# SchematicDoc.net
KiCad netlist of a schematic drawn in Altium Designer
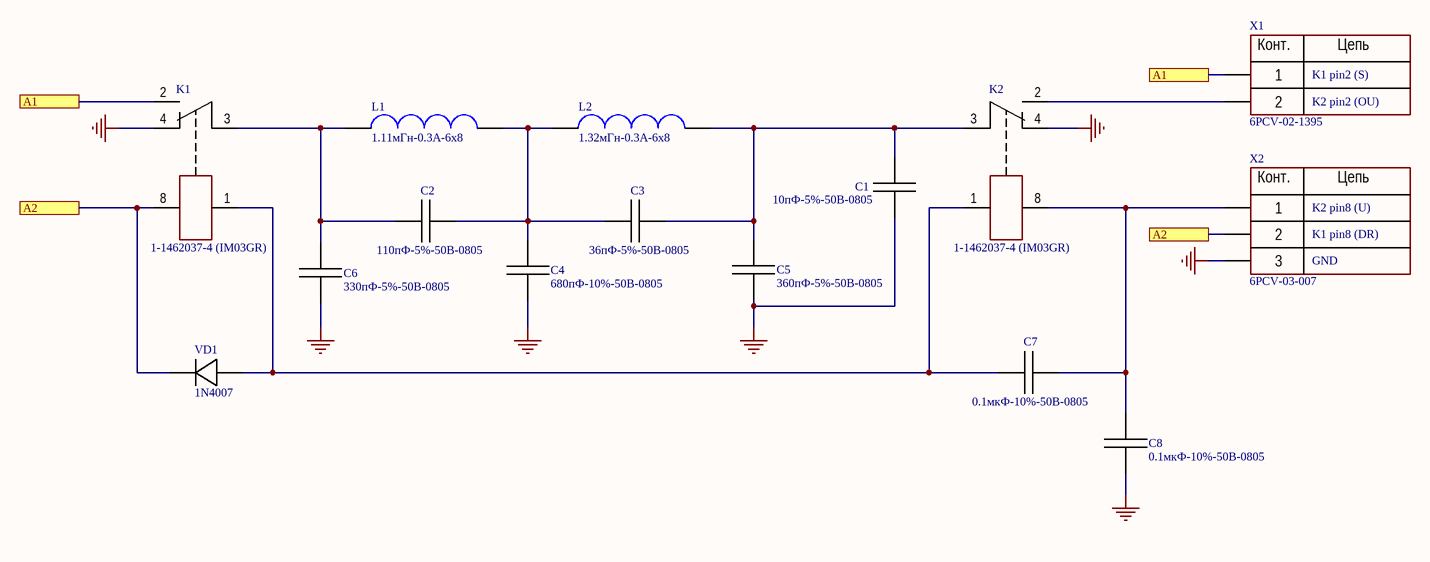
[diagram p0: SchematicDoc.SchDoc]

(export (version "E")
  (design (tool "Eeschema 10.0.6"))
  (components
    (comp (ref "C1")
      (value "10пФ-5%-50В-0805")
      (footprint "CAPAC_0805C")
      (fields
        (field (name "MANUFACTURER") "Murata Electronics")
        (field (name "PARTNUMBER") "GRM2165C1H100JZ01D")
      )
      (libsource (lib "SchematicLib") (part "Capac_0805C"))
    )
    (comp (ref "C2")
      (value "110пФ-5%-50В-0805")
      (footprint "CAPAC_0805C")
      (fields (field (name "MANUFACTURER") "Тайвань") (field (name "PARTNUMBER") "MLCC110pFNPO50V5%0805"))
      (libsource (lib "SchematicLib") (part "Capac_0805C"))
    )
    (comp (ref "C3")
      (value "36пФ-5%-50В-0805")
      (footprint "CAPAC_0805C")
      (fields (field (name "MANUFACTURER") "Тайвань") (field (name "PARTNUMBER") "MLCC36pFNPO50V5%0805"))
      (libsource (lib "SchematicLib") (part "Capac_0805C"))
    )
    (comp (ref "C4")
      (value "680пФ-10%-50В-0805")
      (footprint "CAPAC_0805C")
      (fields
        (field (name "MANUFACTURER") "Murata Electronics")
        (field (name "PARTNUMBER") "GRM216R71H681KA01D")
      )
      (libsource (lib "SchematicLib") (part "Capac_0805C"))
    )
    (comp (ref "C5")
      (value "360пФ-5%-50В-0805")
      (footprint "CAPAC_0805C")
      (fields
        (field (name "MANUFACTURER") "Murata Electronics")
        (field (name "PARTNUMBER") "GRM2165C1H360JZ01D")
      )
      (libsource (lib "SchematicLib") (part "Capac_0805C"))
    )
    (comp (ref "C6")
      (value "330пФ-5%-50В-0805")
      (footprint "CAPAC_0805C")
      (fields
        (field (name "MANUFACTURER") "Murata Electronics")
        (field (name "PARTNUMBER") "GRM2165C1H331JA01D")
      )
      (libsource (lib "SchematicLib") (part "Capac_0805C"))
    )
    (comp (ref "C7")
      (value "0.1мкФ-10%-50В-0805")
      (footprint "CAPAC_0805C")
      (fields
        (field (name "MANUFACTURER") "Murata Electronics")
        (field (name "PARTNUMBER") "GRM21BR71H104KA01L")
      )
      (libsource (lib "SchematicLib") (part "Capac_0805C"))
    )
    (comp (ref "C8")
      (value "0.1мкФ-10%-50В-0805")
      (footprint "CAPAC_0805C")
      (fields
        (field (name "MANUFACTURER") "Murata Electronics")
        (field (name "PARTNUMBER") "GRM21BR71H104KA01L")
      )
      (libsource (lib "SchematicLib") (part "Capac_0805C"))
    )
    (comp (ref "K1")
      (value "1-1462037-4 (IM03GR)")
      (footprint "RELAY_IM03GR")
      (fields (field (name "MANUFACTURER") "TE Connectivity"))
      (libsource (lib "SchematicLib") (part "Realy_IM03GR"))
    )
    (comp (ref "K2")
      (value "1-1462037-4 (IM03GR)")
      (footprint "RELAY_IM03GR")
      (fields (field (name "MANUFACTURER") "TE Connectivity"))
      (libsource (lib "") (part "Realy_IM03GR_1"))
    )
    (comp (ref "L1")
      (value "1.11мГн-0.3А-6x8")
      (footprint "INDUCTOR_6x8")
      (fields (field (name "MANUFACTURER") "QBYDIY"))
      (libsource (lib "SchematicLib") (part "Induc_0805I"))
    )
    (comp (ref "L2")
      (value "1.32мГн-0.3А-6x8")
      (footprint "INDUCTOR_6x8")
      (fields (field (name "MANUFACTURER") "QBYDIY"))
      (libsource (lib "SchematicLib") (part "Induc_0805I"))
    )
    (comp (ref "VD1")
      (value "1N4007")
      (footprint "DIODE_DO-41")
      (fields (field (name "MANUFACTURER") "Diotec Semiconductor"))
      (libsource (lib "SchematicLib") (part "Diode"))
    )
    (comp (ref "X1")
      (value "6PCV-02-1395")
      (footprint "CON_6PCV-02-006")
      (fields (field (name "MANUFACTURER") "TE Connectivity"))
      (libsource (lib "SchematicLib") (part "Con_2"))
    )
    (comp (ref "X2")
      (value "6PCV-03-007")
      (footprint "CON_6PCV-03-006")
      (fields (field (name "MANUFACTURER") "TE Connectivity"))
      (libsource (lib "SchematicLib") (part "Con_3"))
    )
  )
  (nets
    (net (code "1") (name "/A1") (class "Default")
      (node (ref "K1") (pin "2") (pinfunction "2_2") (pintype "passive"))
      (node (ref "X1") (pin "1") (pinfunction "1_1") (pintype "passive"))
    )
    (net (code "2") (name "/A2") (class "Default")
      (node (ref "K1") (pin "8") (pinfunction "8_8") (pintype "passive"))
      (node (ref "VD1") (pin "1") (pinfunction "1_1") (pintype "passive"))
      (node (ref "X2") (pin "2") (pinfunction "2_2") (pintype "passive"))
    )
    (net (code "3") (name "GND") (class "Default")
      (node (ref "C1") (pin "0") (pinfunction "0_0") (pintype "passive"))
      (node (ref "C4") (pin "0") (pinfunction "0_0") (pintype "passive"))
      (node (ref "C5") (pin "0") (pinfunction "0_0") (pintype "passive"))
      (node (ref "C6") (pin "0") (pinfunction "0_0") (pintype "passive"))
      (node (ref "C8") (pin "0") (pinfunction "0_0") (pintype "passive"))
      (node (ref "K1") (pin "4") (pinfunction "4_4") (pintype "passive"))
      (node (ref "K2") (pin "4") (pinfunction "4_4") (pintype "passive"))
      (node (ref "X2") (pin "3") (pinfunction "3_3") (pintype "power_in"))
    )
    (net (code "4") (name "Net-(C2-Pad0)") (class "Default")
      (node (ref "C2") (pin "0") (pinfunction "0_0") (pintype "passive"))
      (node (ref "C3") (pin "0") (pinfunction "0_0") (pintype "passive"))
      (node (ref "C4") (pin "1") (pinfunction "1_1") (pintype "passive"))
      (node (ref "L1") (pin "1") (pinfunction "1_1") (pintype "passive"))
      (node (ref "L2") (pin "0") (pinfunction "0_0") (pintype "passive"))
    )
    (net (code "5") (name "Net-(C7-Pad0)") (class "Default")
      (node (ref "C7") (pin "0") (pinfunction "0_0") (pintype "passive"))
      (node (ref "K1") (pin "1") (pinfunction "1_1") (pintype "passive"))
      (node (ref "K2") (pin "1") (pinfunction "1_1") (pintype "passive"))
      (node (ref "VD1") (pin "0") (pinfunction "0_0") (pintype "passive"))
    )
    (net (code "6") (name "Net-(C7-Pad1)") (class "Default")
      (node (ref "C7") (pin "1") (pinfunction "1_1") (pintype "passive"))
      (node (ref "C8") (pin "1") (pinfunction "1_1") (pintype "passive"))
      (node (ref "K2") (pin "8") (pinfunction "8_8") (pintype "passive"))
      (node (ref "X2") (pin "1") (pinfunction "1_1") (pintype "passive"))
    )
    (net (code "7") (name "Net-(K1-3(6))") (class "Default")
      (node (ref "C2") (pin "1") (pinfunction "1_1") (pintype "passive"))
      (node (ref "C6") (pin "1") (pinfunction "1_1") (pintype "passive"))
      (node (ref "K1") (pin "3") (pinfunction "3(6)_3") (pintype "passive"))
      (node (ref "L1") (pin "0") (pinfunction "0_0") (pintype "passive"))
    )
    (net (code "8") (name "Net-(K2-3(6))") (class "Default")
      (node (ref "C1") (pin "1") (pinfunction "1_1") (pintype "passive"))
      (node (ref "C3") (pin "1") (pinfunction "1_1") (pintype "passive"))
      (node (ref "C5") (pin "1") (pinfunction "1_1") (pintype "passive"))
      (node (ref "K2") (pin "3") (pinfunction "3(6)_3") (pintype "passive"))
      (node (ref "L2") (pin "1") (pinfunction "1_1") (pintype "passive"))
    )
    (net (code "9") (name "Net-(K2-Pad2)") (class "Default")
      (node (ref "K2") (pin "2") (pinfunction "2_2") (pintype "passive"))
      (node (ref "X1") (pin "2") (pinfunction "2_2") (pintype "passive"))
    )
  )
)
